# Voeding.net
KiCad netlist of a schematic drawn in Altium Designer
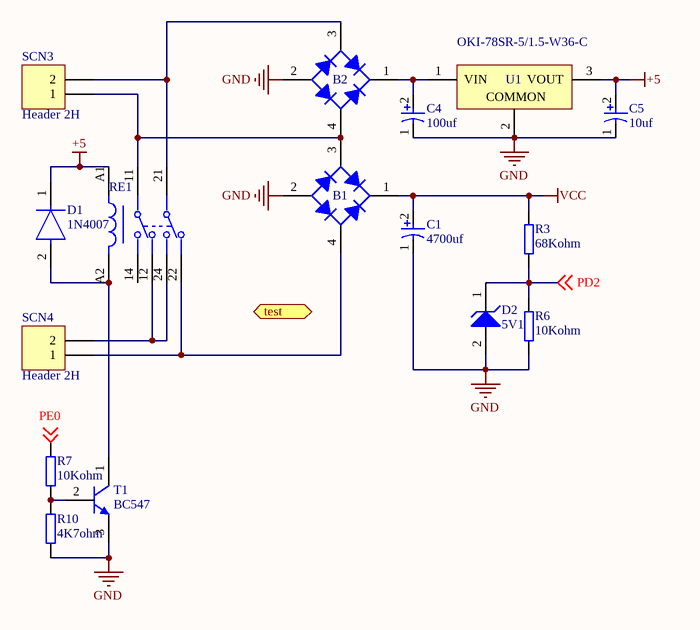
[diagram p0: Voeding.SchDoc]

(export (version "E")
  (design (tool "Eeschema 10.0.6"))
  (components
    (comp (ref "B1")
      (value "Bridge_Rectifier")
      (footprint "ttf")
      (fields (field (name "MANUFACTURER") "Diodes Inc"))
      (libsource (lib "Soldeerstation_Final") (part "Bridge_Rectifier"))
    )
    (comp (ref "B2")
      (value "Bridge_Rectifier")
      (footprint "ttf")
      (fields (field (name "MANUFACTURER") "Diodes Inc"))
      (libsource (lib "Soldeerstation_Final") (part "Bridge_Rectifier"))
    )
    (comp (ref "C1")
      (value "4700uf")
      (footprint "CE_D25_L25_THT")
      (fields (field (name "MANUFACTURER") "Panasonic"))
      (libsource (lib "Soldeerstation_Final") (part "Capacitor_Electrolytic"))
    )
    (comp (ref "C4")
      (value "100uf")
      (footprint "CE_D8_L10")
      (fields (field (name "MANUFACTURER") "Panasonic"))
      (libsource (lib "Soldeerstation_Final") (part "Capacitor_Electrolytic"))
    )
    (comp (ref "C5")
      (value "10uf")
      (footprint "CE_D4_L5,4")
      (fields (field (name "MANUFACTURER") "Panasonic"))
      (libsource (lib "Soldeerstation_Final") (part "Capacitor_Electrolytic"))
    )
    (comp (ref "D1")
      (value "1N4007")
      (footprint "SOD-123FL")
      (fields
        (field (name "MANUFACTURER") "Diotec")
        (field (name "OCTOPART") "https://octopart.com/1n4007-diotec-4040411")
      )
      (libsource (lib "Soldeerstation_Final") (part "Diode"))
    )
    (comp (ref "D2")
      (value "5V1")
      (footprint "SOD-123FL")
      (fields (field (name "MANUFACTURER") "On Semiconductor") (field (name "PARTNUMBER") "1SMB5920BT3G"))
      (libsource (lib "Soldeerstation_Final") (part "Zener_Diode"))
    )
    (comp (ref "R3")
      (value "68Kohm")
      (footprint "R_0805_M")
      (fields (field (name "MANUFACTURER") "Vishay Dale") (field (name "PART NUMBER") "CRCW08050000Z0EA"))
      (libsource (lib "Soldeerstation_Final") (part "Resistor"))
    )
    (comp (ref "R6")
      (value "10Kohm")
      (footprint "R_0805_M")
      (fields (field (name "MANUFACTURER") "Vishay Dale") (field (name "PART NUMBER") "CRCW08050000Z0EA"))
      (libsource (lib "Soldeerstation_Final") (part "Resistor"))
    )
    (comp (ref "R7")
      (value "10Kohm")
      (footprint "R_0805_M")
      (fields (field (name "MANUFACTURER") "Vishay Dale") (field (name "PART NUMBER") "CRCW08050000Z0EA"))
      (libsource (lib "Soldeerstation_Final") (part "Resistor"))
    )
    (comp (ref "R10")
      (value "4K7ohm")
      (footprint "R_0805_M")
      (fields (field (name "MANUFACTURER") "Vishay Dale") (field (name "PART NUMBER") "CRCW08050000Z0EA"))
      (libsource (lib "Soldeerstation_Final") (part "Resistor"))
    )
    (comp (ref "RE1")
      (value "RELAY_GENERAL_PURPOSE")
      (footprint "RT42")
      (fields
        (field (name "MANUFACTURER PART NUMBER") "RT424005")
        (field (name "OCTOPART") "https://octopart.com/5-1393243-9-te+connectivity-41835766")
        (field (name "MANUFACTURER") "TE Connectivity")
      )
      (libsource (lib "Soldeerstation_Final") (part "RELAY_GENERAL_PURPOSE"))
    )
    (comp (ref "SCN3")
      (value "Header 2H")
      (footprint "Connector_2x1_p_5mm")
      (description "ScrewConnector, 2-Pin, Right Angle")
      (fields (field (name "PUBLISHER") "Altium Limited"))
      (libsource (lib "Miscellaneous Connectors") (part "Header 2H"))
    )
    (comp (ref "SCN4")
      (value "Header 2H")
      (footprint "Connector_2x1_p_5mm")
      (description "ScrewConnector, 2-Pin, Right Angle")
      (fields (field (name "PUBLISHER") "Altium Limited"))
      (libsource (lib "Miscellaneous Connectors") (part "Header 2H"))
    )
    (comp (ref "T1")
      (value "BC547")
      (footprint "SOT_23")
      (fields (field (name "MANUFACTURER") "On Semiconductor") (field (name "PARTNUMBER") "BC547C"))
      (libsource (lib "Soldeerstation_Final") (part "Transistor_NPN"))
    )
    (comp (ref "U1")
      (value "OKI-78SR-5/1.5-W36-C")
      (footprint "OKI78SR515W36C")
      (fields (field (name "MANUFACTURER") "Murata"))
      (libsource (lib "Soldeerstation_Final") (part "DC/DC Converter"))
    )
  )
  (nets
    (net (code "1") (name "+5") (class "Default")
      (node (ref "C5") (pin "2") (pinfunction "2_2") (pintype "passive"))
      (node (ref "D1") (pin "1") (pinfunction "C_1") (pintype "passive"))
      (node (ref "RE1") (pin "A1") (pinfunction "A1_A1") (pintype "passive"))
      (node (ref "U1") (pin "3") (pinfunction "VOUT_3") (pintype "power_in"))
    )
    (net (code "3") (name "GND") (class "Default")
      (node (ref "B1") (pin "2") (pinfunction "A_2") (pintype "passive"))
      (node (ref "B2") (pin "2") (pinfunction "A_2") (pintype "passive"))
      (node (ref "C1") (pin "1") (pinfunction "1_1") (pintype "passive"))
      (node (ref "C4") (pin "1") (pinfunction "1_1") (pintype "passive"))
      (node (ref "C5") (pin "1") (pinfunction "1_1") (pintype "passive"))
      (node (ref "D2") (pin "2") (pinfunction "A_2") (pintype "passive"))
      (node (ref "R10") (pin "2") (pinfunction "2_2") (pintype "passive"))
      (node (ref "R6") (pin "2") (pinfunction "2_2") (pintype "passive"))
      (node (ref "T1") (pin "3") (pinfunction "E_3") (pintype "passive"))
      (node (ref "U1") (pin "2") (pinfunction "COMMON_2") (pintype "power_in"))
    )
    (net (code "4") (name "Net-(B1-C-Pad3)") (class "Default")
      (node (ref "B1") (pin "3") (pinfunction "C_3") (pintype "passive"))
      (node (ref "B2") (pin "4") (pinfunction "C_4") (pintype "passive"))
      (node (ref "RE1") (pin "11") (pinfunction "11_11") (pintype "passive"))
      (node (ref "SCN3") (pin "1") (pinfunction "1_1") (pintype "passive"))
    )
    (net (code "5") (name "Net-(B1-C-Pad4)") (class "Default")
      (node (ref "B1") (pin "4") (pinfunction "C_4") (pintype "passive"))
      (node (ref "RE1") (pin "22") (pinfunction "22_22") (pintype "passive"))
      (node (ref "SCN4") (pin "1") (pinfunction "1_1") (pintype "passive"))
    )
    (net (code "6") (name "Net-(B2-C-Pad3)") (class "Default")
      (node (ref "B2") (pin "3") (pinfunction "C_3") (pintype "passive"))
      (node (ref "RE1") (pin "21") (pinfunction "21_21") (pintype "passive"))
      (node (ref "SCN3") (pin "2") (pinfunction "2_2") (pintype "passive"))
    )
    (net (code "7") (name "Net-(B2-K)") (class "Default")
      (node (ref "B2") (pin "1") (pinfunction "K_1") (pintype "passive"))
      (node (ref "C4") (pin "2") (pinfunction "2_2") (pintype "passive"))
      (node (ref "U1") (pin "1") (pinfunction "VIN_1") (pintype "power_in"))
    )
    (net (code "8") (name "Net-(D1-A)") (class "Default")
      (node (ref "D1") (pin "2") (pinfunction "A_2") (pintype "passive"))
      (node (ref "RE1") (pin "A2") (pinfunction "A2_A2") (pintype "passive"))
      (node (ref "T1") (pin "1") (pinfunction "C_1") (pintype "passive"))
    )
    (net (code "9") (name "Net-(RE1-Pad12)") (class "Default")
      (node (ref "RE1") (pin "12") (pinfunction "12_12") (pintype "passive"))
      (node (ref "RE1") (pin "24") (pinfunction "24_24") (pintype "passive"))
      (node (ref "SCN4") (pin "2") (pinfunction "2_2") (pintype "passive"))
    )
    (net (code "10") (name "Net-(T1-B)") (class "Default")
      (node (ref "R10") (pin "1") (pinfunction "1_1") (pintype "passive"))
      (node (ref "R7") (pin "1") (pinfunction "1_1") (pintype "passive"))
      (node (ref "T1") (pin "2") (pinfunction "B_2") (pintype "passive"))
    )
    (net (code "11") (name "PD2") (class "Default")
      (node (ref "D2") (pin "1") (pinfunction "K_1") (pintype "passive"))
      (node (ref "R3") (pin "1") (pinfunction "1_1") (pintype "passive"))
      (node (ref "R6") (pin "1") (pinfunction "1_1") (pintype "passive"))
    )
    (net (code "12") (name "PE0") (class "Default")
      (node (ref "R7") (pin "2") (pinfunction "2_2") (pintype "passive"))
    )
    (net (code "13") (name "VCC") (class "Default")
      (node (ref "B1") (pin "1") (pinfunction "K_1") (pintype "passive"))
      (node (ref "C1") (pin "2") (pinfunction "2_2") (pintype "passive"))
      (node (ref "R3") (pin "2") (pinfunction "2_2") (pintype "passive"))
    )
    (net (code "14") (name "unconnected-(RE1-Pad14)") (class "Default")
      (node (ref "RE1") (pin "14") (pinfunction "14_14") (pintype "passive"))
    )
  )
)
